# beaconboard2.net
KiCad netlist of a schematic drawn in EAGLE
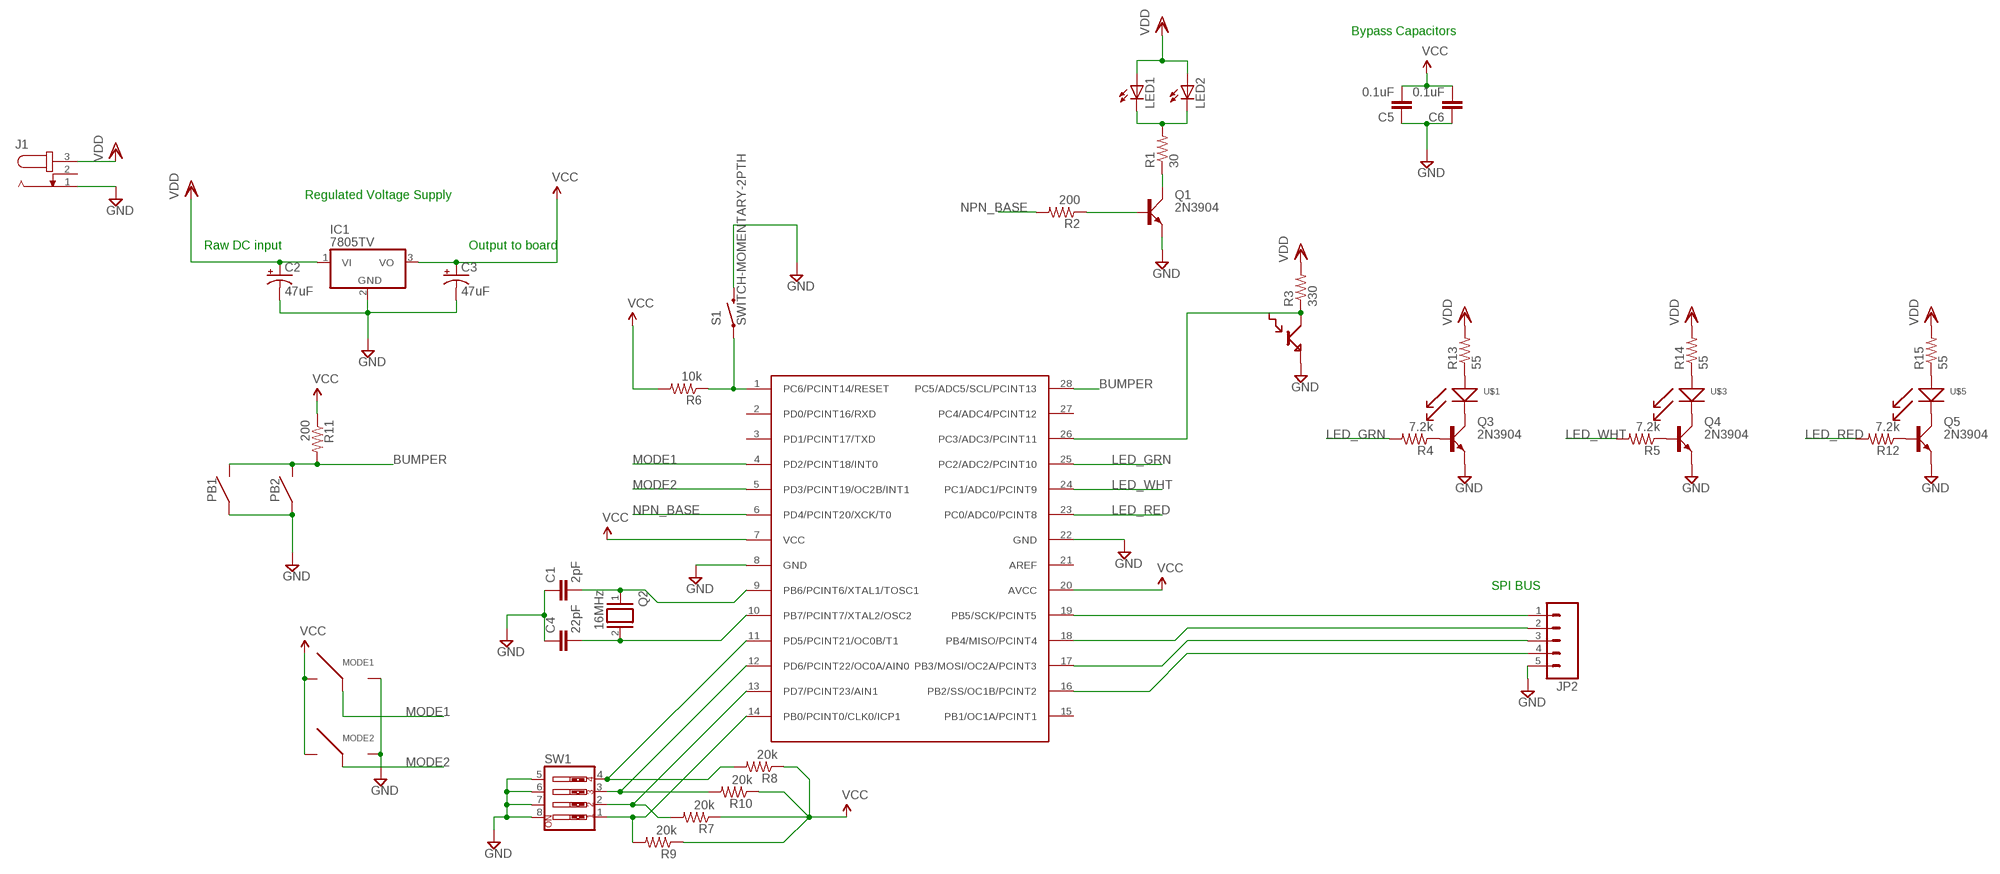
[diagram p0: schematic, sheet 1]

(export (version "E")
  (design (tool "Eeschema 10.0.6"))
  (components
    (comp (ref "C1")
      (value "2pF")
      (footprint "eagle-import:CAP-PTH-SMALL")
      (libsource (lib "eagle-import") (part "CAPPTH"))
    )
    (comp (ref "C2")
      (value "47uF")
      (footprint "eagle-import:CPOL-RADIAL-10UF-25V")
      (libsource (lib "eagle-import") (part "CAP_POLPTH2"))
    )
    (comp (ref "C3")
      (value "47uF")
      (footprint "eagle-import:CPOL-RADIAL-10UF-25V")
      (libsource (lib "eagle-import") (part "CAP_POLPTH2"))
    )
    (comp (ref "C4")
      (value "22pF")
      (footprint "eagle-import:CAP-PTH-SMALL")
      (libsource (lib "eagle-import") (part "CAPPTH"))
    )
    (comp (ref "C5")
      (value "0.1uF")
      (footprint "eagle-import:CAP-PTH-5MM")
      (libsource (lib "eagle-import") (part "CAPPTH1"))
    )
    (comp (ref "C6")
      (value "0.1uF")
      (footprint "eagle-import:CAP-PTH-5MM")
      (libsource (lib "eagle-import") (part "CAPPTH1"))
    )
    (comp (ref "IC1")
      (value "7805TV")
      (footprint "eagle-import:TO220V")
      (libsource (lib "eagle-import") (part "78TV05"))
    )
    (comp (ref "J1")
      (value "JACK-PLUG1")
      (footprint "eagle-import:SPC4078")
      (libsource (lib "eagle-import") (part "JACK-PLUG1"))
    )
    (comp (ref "JP2")
      (value "M05LOCK_LONGPADS")
      (footprint "eagle-import:1X05_LOCK_LONGPADS")
      (libsource (lib "eagle-import") (part "M05LOCK_LONGPADS"))
    )
    (comp (ref "LED1")
      (value "LED-2AC-CP41B-WES")
      (footprint "eagle-import:CP41B")
      (libsource (lib "eagle-import") (part "LED-2AC-CP41B-WES"))
    )
    (comp (ref "LED2")
      (value "LED-2AC-CP41B-WES")
      (footprint "eagle-import:CP41B")
      (libsource (lib "eagle-import") (part "LED-2AC-CP41B-WES"))
    )
    (comp (ref "MODE1")
      (value "SPD_SLIDE_SWITCH")
      (footprint "eagle-import:SPDT_SLIDE_SWITCH")
      (libsource (lib "eagle-import") (part "SPD_SLIDE_SWITCH"))
    )
    (comp (ref "MODE2")
      (value "SPD_SLIDE_SWITCH")
      (footprint "eagle-import:SPDT_SLIDE_SWITCH")
      (libsource (lib "eagle-import") (part "SPD_SLIDE_SWITCH"))
    )
    (comp (ref "PB1")
      (value "D6_PUSHBUTTON")
      (footprint "eagle-import:D6_PUSH_BUTTON")
      (libsource (lib "eagle-import") (part "D6_PUSHBUTTON"))
    )
    (comp (ref "PB2")
      (value "D6_PUSHBUTTON")
      (footprint "eagle-import:D6_PUSH_BUTTON")
      (libsource (lib "eagle-import") (part "D6_PUSHBUTTON"))
    )
    (comp (ref "Q1")
      (value "2N3904")
      (footprint "eagle-import:TO92D")
      (libsource (lib "eagle-import") (part "2N3904"))
    )
    (comp (ref "Q2")
      (value "16MHz")
      (footprint "eagle-import:QS")
      (libsource (lib "eagle-import") (part "XTAL/S"))
    )
    (comp (ref "Q3")
      (value "2N3904")
      (footprint "eagle-import:TO92D")
      (libsource (lib "eagle-import") (part "2N3904"))
    )
    (comp (ref "Q4")
      (value "2N3904")
      (footprint "eagle-import:TO92D")
      (libsource (lib "eagle-import") (part "2N3904"))
    )
    (comp (ref "Q5")
      (value "2N3904")
      (footprint "eagle-import:TO92D")
      (libsource (lib "eagle-import") (part "2N3904"))
    )
    (comp (ref "R1")
      (value "30")
      (footprint "eagle-import:AXIAL-0.4")
      (libsource (lib "eagle-import") (part "RESISTORPTH-1/4W"))
    )
    (comp (ref "R2")
      (value "200")
      (footprint "eagle-import:AXIAL-0.4")
      (libsource (lib "eagle-import") (part "RESISTORPTH-1/4W"))
    )
    (comp (ref "R3")
      (value "330")
      (footprint "eagle-import:AXIAL-0.4")
      (libsource (lib "eagle-import") (part "RESISTORPTH-1/4W"))
    )
    (comp (ref "R4")
      (value "7.2k")
      (footprint "eagle-import:AXIAL-0.4")
      (libsource (lib "eagle-import") (part "RESISTORPTH-1/4W"))
    )
    (comp (ref "R5")
      (value "7.2k")
      (footprint "eagle-import:AXIAL-0.4")
      (libsource (lib "eagle-import") (part "RESISTORPTH-1/4W"))
    )
    (comp (ref "R6")
      (value "10k")
      (footprint "eagle-import:AXIAL-0.4")
      (libsource (lib "eagle-import") (part "RESISTORPTH-1/4W"))
    )
    (comp (ref "R7")
      (value "20k")
      (footprint "eagle-import:AXIAL-0.4")
      (libsource (lib "eagle-import") (part "RESISTORPTH-1/4W"))
    )
    (comp (ref "R8")
      (value "20k")
      (footprint "eagle-import:AXIAL-0.4")
      (libsource (lib "eagle-import") (part "RESISTORPTH-1/4W"))
    )
    (comp (ref "R9")
      (value "20k")
      (footprint "eagle-import:AXIAL-0.4")
      (libsource (lib "eagle-import") (part "RESISTORPTH-1/4W"))
    )
    (comp (ref "R10")
      (value "20k")
      (footprint "eagle-import:AXIAL-0.4")
      (libsource (lib "eagle-import") (part "RESISTORPTH-1/4W"))
    )
    (comp (ref "R11")
      (value "200")
      (footprint "eagle-import:AXIAL-0.4")
      (libsource (lib "eagle-import") (part "RESISTORPTH-1/4W"))
    )
    (comp (ref "R12")
      (value "7.2k")
      (footprint "eagle-import:AXIAL-0.4")
      (libsource (lib "eagle-import") (part "RESISTORPTH-1/4W"))
    )
    (comp (ref "R13")
      (value "55")
      (footprint "eagle-import:AXIAL-0.4")
      (libsource (lib "eagle-import") (part "RESISTORPTH-1/4W"))
    )
    (comp (ref "R14")
      (value "55")
      (footprint "eagle-import:AXIAL-0.4")
      (libsource (lib "eagle-import") (part "RESISTORPTH-1/4W"))
    )
    (comp (ref "R15")
      (value "55")
      (footprint "eagle-import:AXIAL-0.4")
      (libsource (lib "eagle-import") (part "RESISTORPTH-1/4W"))
    )
    (comp (ref "S1")
      (value "SWITCH-MOMENTARY-2PTH")
      (footprint "eagle-import:TACTILE-PTH")
      (libsource (lib "eagle-import") (part "SWITCH-MOMENTARY-2PTH"))
    )
    (comp (ref "SW1")
      (value "SW_DIP-4")
      (footprint "eagle-import:EDG-04")
      (libsource (lib "eagle-import") (part "SW_DIP-4"))
    )
    (comp (ref "U$1")
      (value "8MM_LED")
      (footprint "eagle-import:8MM_LED")
      (libsource (lib "eagle-import") (part "8MM_LED"))
    )
    (comp (ref "U$2")
      (value "BPW77NA")
      (footprint "eagle-import:TO-18")
      (libsource (lib "eagle-import") (part "BPW77NA"))
    )
    (comp (ref "U$3")
      (value "8MM_LED")
      (footprint "eagle-import:8MM_LED")
      (libsource (lib "eagle-import") (part "8MM_LED"))
    )
    (comp (ref "U$4")
      (value "ATMEGA328")
      (footprint "eagle-import:DIL28-3")
      (libsource (lib "eagle-import") (part "ATMEGA328"))
    )
    (comp (ref "U$5")
      (value "8MM_LED")
      (footprint "eagle-import:8MM_LED")
      (libsource (lib "eagle-import") (part "8MM_LED"))
    )
  )
  (nets
    (net (code "1") (name "/BUMPER") (class "Default")
      (node (ref "PB1") (pin "3") (pinfunction "2_3") (pintype "bidirectional"))
      (node (ref "PB1") (pin "4") (pinfunction "2_4") (pintype "bidirectional"))
      (node (ref "PB2") (pin "3") (pinfunction "2_3") (pintype "bidirectional"))
      (node (ref "PB2") (pin "4") (pinfunction "2_4") (pintype "bidirectional"))
      (node (ref "R11") (pin "P$2") (pinfunction "2_P$2") (pintype "passive"))
      (node (ref "U$4") (pin "28") (pinfunction "PC5/ADC5/SCL/PCINT13_28") (pintype "bidirectional"))
    )
    (net (code "2") (name "/LED_GRN") (class "Default")
      (node (ref "R4") (pin "P$2") (pinfunction "2_P$2") (pintype "passive"))
      (node (ref "U$4") (pin "25") (pinfunction "PC2/ADC2/PCINT10_25") (pintype "bidirectional"))
    )
    (net (code "3") (name "/LED_RED") (class "Default")
      (node (ref "R12") (pin "P$2") (pinfunction "2_P$2") (pintype "passive"))
      (node (ref "U$4") (pin "23") (pinfunction "PC0/ADC0/PCINT8_23") (pintype "bidirectional"))
    )
    (net (code "4") (name "/LED_WHT") (class "Default")
      (node (ref "R5") (pin "P$2") (pinfunction "2_P$2") (pintype "passive"))
      (node (ref "U$4") (pin "24") (pinfunction "PC1/ADC1/PCINT9_24") (pintype "bidirectional"))
    )
    (net (code "5") (name "/MODE1") (class "Default")
      (node (ref "MODE1") (pin "2") (pinfunction "2_2") (pintype "bidirectional"))
      (node (ref "U$4") (pin "4") (pinfunction "PD2/PCINT18/INT0_4") (pintype "bidirectional"))
    )
    (net (code "6") (name "/MODE2") (class "Default")
      (node (ref "MODE2") (pin "2") (pinfunction "2_2") (pintype "bidirectional"))
      (node (ref "U$4") (pin "5") (pinfunction "PD3/PCINT19/OC2B/INT1_5") (pintype "bidirectional"))
    )
    (net (code "7") (name "/NPN_BASE") (class "Default")
      (node (ref "R2") (pin "P$2") (pinfunction "2_P$2") (pintype "passive"))
      (node (ref "U$4") (pin "6") (pinfunction "PD4/PCINT20/XCK/T0_6") (pintype "bidirectional"))
    )
    (net (code "8") (name "GND") (class "Default")
      (node (ref "C1") (pin "1") (pinfunction "1_1") (pintype "passive"))
      (node (ref "C2") (pin "2") (pinfunction "-_2") (pintype "passive"))
      (node (ref "C3") (pin "2") (pinfunction "-_2") (pintype "passive"))
      (node (ref "C4") (pin "1") (pinfunction "1_1") (pintype "passive"))
      (node (ref "C5") (pin "1") (pinfunction "1_1") (pintype "passive"))
      (node (ref "C6") (pin "1") (pinfunction "1_1") (pintype "passive"))
      (node (ref "IC1") (pin "2") (pinfunction "GND_2") (pintype "passive"))
      (node (ref "J1") (pin "1") (pinfunction "1_1") (pintype "passive"))
      (node (ref "JP2") (pin "5") (pinfunction "5_5") (pintype "passive"))
      (node (ref "MODE1") (pin "3") (pinfunction "3_3") (pintype "bidirectional"))
      (node (ref "MODE2") (pin "3") (pinfunction "3_3") (pintype "bidirectional"))
      (node (ref "PB1") (pin "1") (pinfunction "1_1") (pintype "bidirectional"))
      (node (ref "PB1") (pin "2") (pinfunction "1_2") (pintype "bidirectional"))
      (node (ref "PB2") (pin "1") (pinfunction "1_1") (pintype "bidirectional"))
      (node (ref "PB2") (pin "2") (pinfunction "1_2") (pintype "bidirectional"))
      (node (ref "Q1") (pin "E") (pinfunction "E_E") (pintype "passive"))
      (node (ref "Q3") (pin "E") (pinfunction "E_E") (pintype "passive"))
      (node (ref "Q4") (pin "E") (pinfunction "E_E") (pintype "passive"))
      (node (ref "Q5") (pin "E") (pinfunction "E_E") (pintype "passive"))
      (node (ref "S1") (pin "3") (pinfunction "2_3") (pintype "passive"))
      (node (ref "SW1") (pin "5") (pinfunction "5_5") (pintype "passive"))
      (node (ref "SW1") (pin "6") (pinfunction "6_6") (pintype "passive"))
      (node (ref "SW1") (pin "7") (pinfunction "7_7") (pintype "passive"))
      (node (ref "SW1") (pin "8") (pinfunction "8_8") (pintype "passive"))
      (node (ref "U$2") (pin "E") (pinfunction "E_E") (pintype "bidirectional"))
      (node (ref "U$4") (pin "22") (pinfunction "GND_22") (pintype "power_in"))
      (node (ref "U$4") (pin "8") (pinfunction "GND_8") (pintype "power_in"))
    )
    (net (code "9") (name "Net-(Q3-PadC)") (class "Default")
      (node (ref "Q3") (pin "C") (pinfunction "C_C") (pintype "passive"))
      (node (ref "U$1") (pin "NEG") (pinfunction "NEG_NEG") (pintype "bidirectional"))
    )
    (net (code "10") (name "Net-(Q4-PadC)") (class "Default")
      (node (ref "Q4") (pin "C") (pinfunction "C_C") (pintype "passive"))
      (node (ref "U$3") (pin "NEG") (pinfunction "NEG_NEG") (pintype "bidirectional"))
    )
    (net (code "11") (name "Net-(Q5-PadC)") (class "Default")
      (node (ref "Q5") (pin "C") (pinfunction "C_C") (pintype "passive"))
      (node (ref "U$5") (pin "NEG") (pinfunction "NEG_NEG") (pintype "bidirectional"))
    )
    (net (code "12") (name "Net-(R1-1)") (class "Default")
      (node (ref "Q1") (pin "C") (pinfunction "C_C") (pintype "passive"))
      (node (ref "R1") (pin "P$1") (pinfunction "1_P$1") (pintype "passive"))
    )
    (net (code "13") (name "Net-(R1-2)") (class "Default")
      (node (ref "LED1") (pin "1") (pinfunction "C_1") (pintype "passive"))
      (node (ref "LED1") (pin "4") (pinfunction "C_4") (pintype "passive"))
      (node (ref "LED2") (pin "1") (pinfunction "C_1") (pintype "passive"))
      (node (ref "LED2") (pin "4") (pinfunction "C_4") (pintype "passive"))
      (node (ref "R1") (pin "P$2") (pinfunction "2_P$2") (pintype "passive"))
    )
    (net (code "14") (name "Net-(R2-1)") (class "Default")
      (node (ref "Q1") (pin "B") (pinfunction "B_B") (pintype "passive"))
      (node (ref "R2") (pin "P$1") (pinfunction "1_P$1") (pintype "passive"))
    )
    (net (code "15") (name "Net-(R3-1)") (class "Default")
      (node (ref "R3") (pin "P$1") (pinfunction "1_P$1") (pintype "passive"))
      (node (ref "U$2") (pin "C") (pinfunction "C_C") (pintype "bidirectional"))
      (node (ref "U$4") (pin "26") (pinfunction "PC3/ADC3/PCINT11_26") (pintype "bidirectional"))
    )
    (net (code "16") (name "Net-(R4-1)") (class "Default")
      (node (ref "Q3") (pin "B") (pinfunction "B_B") (pintype "passive"))
      (node (ref "R4") (pin "P$1") (pinfunction "1_P$1") (pintype "passive"))
    )
    (net (code "17") (name "Net-(R5-1)") (class "Default")
      (node (ref "Q4") (pin "B") (pinfunction "B_B") (pintype "passive"))
      (node (ref "R5") (pin "P$1") (pinfunction "1_P$1") (pintype "passive"))
    )
    (net (code "18") (name "Net-(R6-1)") (class "Default")
      (node (ref "R6") (pin "P$1") (pinfunction "1_P$1") (pintype "passive"))
      (node (ref "S1") (pin "1") (pinfunction "1_1") (pintype "passive"))
      (node (ref "U$4") (pin "1") (pinfunction "PC6/PCINT14/RESET_1") (pintype "bidirectional"))
    )
    (net (code "19") (name "Net-(R7-2)") (class "Default")
      (node (ref "R7") (pin "P$2") (pinfunction "2_P$2") (pintype "passive"))
      (node (ref "SW1") (pin "2") (pinfunction "2_2") (pintype "passive"))
      (node (ref "U$4") (pin "13") (pinfunction "PD7/PCINT23/AIN1_13") (pintype "bidirectional"))
    )
    (net (code "20") (name "Net-(R8-2)") (class "Default")
      (node (ref "R8") (pin "P$2") (pinfunction "2_P$2") (pintype "passive"))
      (node (ref "SW1") (pin "4") (pinfunction "4_4") (pintype "passive"))
      (node (ref "U$4") (pin "11") (pinfunction "PD5/PCINT21/OC0B/T1_11") (pintype "bidirectional"))
    )
    (net (code "21") (name "Net-(R9-2)") (class "Default")
      (node (ref "R9") (pin "P$2") (pinfunction "2_P$2") (pintype "passive"))
      (node (ref "SW1") (pin "1") (pinfunction "1_1") (pintype "passive"))
      (node (ref "U$4") (pin "14") (pinfunction "PB0/PCINT0/CLK0/ICP1_14") (pintype "bidirectional"))
    )
    (net (code "22") (name "Net-(R10-2)") (class "Default")
      (node (ref "R10") (pin "P$2") (pinfunction "2_P$2") (pintype "passive"))
      (node (ref "SW1") (pin "3") (pinfunction "3_3") (pintype "passive"))
      (node (ref "U$4") (pin "12") (pinfunction "PD6/PCINT22/OC0A/AIN0_12") (pintype "bidirectional"))
    )
    (net (code "23") (name "Net-(R12-1)") (class "Default")
      (node (ref "Q5") (pin "B") (pinfunction "B_B") (pintype "passive"))
      (node (ref "R12") (pin "P$1") (pinfunction "1_P$1") (pintype "passive"))
    )
    (net (code "24") (name "Net-(R13-1)") (class "Default")
      (node (ref "R13") (pin "P$1") (pinfunction "1_P$1") (pintype "passive"))
      (node (ref "U$1") (pin "POS") (pinfunction "POS_POS") (pintype "bidirectional"))
    )
    (net (code "25") (name "Net-(R14-1)") (class "Default")
      (node (ref "R14") (pin "P$1") (pinfunction "1_P$1") (pintype "passive"))
      (node (ref "U$3") (pin "POS") (pinfunction "POS_POS") (pintype "bidirectional"))
    )
    (net (code "26") (name "Net-(R15-1)") (class "Default")
      (node (ref "R15") (pin "P$1") (pinfunction "1_P$1") (pintype "passive"))
      (node (ref "U$5") (pin "POS") (pinfunction "POS_POS") (pintype "bidirectional"))
    )
    (net (code "27") (name "Net-(U$4-PB2{slash}SS{slash}OC1B{slash}PCINT2)") (class "Default")
      (node (ref "JP2") (pin "4") (pinfunction "4_4") (pintype "passive"))
      (node (ref "U$4") (pin "16") (pinfunction "PB2/SS/OC1B/PCINT2_16") (pintype "bidirectional"))
    )
    (net (code "28") (name "Net-(U$4-PB3{slash}MOSI{slash}OC2A{slash}PCINT3)") (class "Default")
      (node (ref "JP2") (pin "3") (pinfunction "3_3") (pintype "passive"))
      (node (ref "U$4") (pin "17") (pinfunction "PB3/MOSI/OC2A/PCINT3_17") (pintype "bidirectional"))
    )
    (net (code "29") (name "Net-(U$4-PB4{slash}MISO{slash}PCINT4)") (class "Default")
      (node (ref "JP2") (pin "2") (pinfunction "2_2") (pintype "passive"))
      (node (ref "U$4") (pin "18") (pinfunction "PB4/MISO/PCINT4_18") (pintype "bidirectional"))
    )
    (net (code "30") (name "Net-(U$4-PB5{slash}SCK{slash}PCINT5)") (class "Default")
      (node (ref "JP2") (pin "1") (pinfunction "1_1") (pintype "passive"))
      (node (ref "U$4") (pin "19") (pinfunction "PB5/SCK/PCINT5_19") (pintype "bidirectional"))
    )
    (net (code "31") (name "Net-(U$4-PB6{slash}PCINT6{slash}XTAL1{slash}TOSC1)") (class "Default")
      (node (ref "C1") (pin "2") (pinfunction "2_2") (pintype "passive"))
      (node (ref "Q2") (pin "1") (pinfunction "1_1") (pintype "passive"))
      (node (ref "U$4") (pin "9") (pinfunction "PB6/PCINT6/XTAL1/TOSC1_9") (pintype "bidirectional"))
    )
    (net (code "32") (name "Net-(U$4-PB7{slash}PCINT7{slash}XTAL2{slash}OSC2)") (class "Default")
      (node (ref "C4") (pin "2") (pinfunction "2_2") (pintype "passive"))
      (node (ref "Q2") (pin "2") (pinfunction "2_2") (pintype "passive"))
      (node (ref "U$4") (pin "10") (pinfunction "PB7/PCINT7/XTAL2/OSC2_10") (pintype "bidirectional"))
    )
    (net (code "33") (name "VCC") (class "Default")
      (node (ref "C3") (pin "1") (pinfunction "+_1") (pintype "passive"))
      (node (ref "C5") (pin "2") (pinfunction "2_2") (pintype "passive"))
      (node (ref "C6") (pin "2") (pinfunction "2_2") (pintype "passive"))
      (node (ref "IC1") (pin "3") (pinfunction "VO_3") (pintype "passive"))
      (node (ref "MODE1") (pin "1") (pinfunction "1_1") (pintype "bidirectional"))
      (node (ref "MODE2") (pin "1") (pinfunction "1_1") (pintype "bidirectional"))
      (node (ref "R10") (pin "P$1") (pinfunction "1_P$1") (pintype "passive"))
      (node (ref "R11") (pin "P$1") (pinfunction "1_P$1") (pintype "passive"))
      (node (ref "R6") (pin "P$2") (pinfunction "2_P$2") (pintype "passive"))
      (node (ref "R7") (pin "P$1") (pinfunction "1_P$1") (pintype "passive"))
      (node (ref "R8") (pin "P$1") (pinfunction "1_P$1") (pintype "passive"))
      (node (ref "R9") (pin "P$1") (pinfunction "1_P$1") (pintype "passive"))
      (node (ref "U$4") (pin "20") (pinfunction "AVCC_20") (pintype "bidirectional"))
      (node (ref "U$4") (pin "7") (pinfunction "VCC_7") (pintype "power_in"))
    )
    (net (code "34") (name "VDD") (class "Default")
      (node (ref "C2") (pin "1") (pinfunction "+_1") (pintype "passive"))
      (node (ref "IC1") (pin "1") (pinfunction "VI_1") (pintype "input"))
      (node (ref "J1") (pin "3") (pinfunction "3_3") (pintype "passive"))
      (node (ref "LED1") (pin "2") (pinfunction "A_2") (pintype "passive"))
      (node (ref "LED1") (pin "3") (pinfunction "A_3") (pintype "passive"))
      (node (ref "LED2") (pin "2") (pinfunction "A_2") (pintype "passive"))
      (node (ref "LED2") (pin "3") (pinfunction "A_3") (pintype "passive"))
      (node (ref "R13") (pin "P$2") (pinfunction "2_P$2") (pintype "passive"))
      (node (ref "R14") (pin "P$2") (pinfunction "2_P$2") (pintype "passive"))
      (node (ref "R15") (pin "P$2") (pinfunction "2_P$2") (pintype "passive"))
      (node (ref "R3") (pin "P$2") (pinfunction "2_P$2") (pintype "passive"))
    )
    (net (code "35") (name "unconnected-(J1-Pad2)") (class "Default")
      (node (ref "J1") (pin "2") (pinfunction "2_2") (pintype "passive"))
    )
    (net (code "36") (name "unconnected-(U$4-AREF-Pad21)") (class "Default")
      (node (ref "U$4") (pin "21") (pinfunction "AREF_21") (pintype "bidirectional"))
    )
    (net (code "37") (name "unconnected-(U$4-PB1{slash}OC1A{slash}PCINT1-Pad15)") (class "Default")
      (node (ref "U$4") (pin "15") (pinfunction "PB1/OC1A/PCINT1_15") (pintype "bidirectional"))
    )
    (net (code "38") (name "unconnected-(U$4-PC4{slash}ADC4{slash}PCINT12-Pad27)") (class "Default")
      (node (ref "U$4") (pin "27") (pinfunction "PC4/ADC4/PCINT12_27") (pintype "bidirectional"))
    )
    (net (code "39") (name "unconnected-(U$4-PD0{slash}PCINT16{slash}RXD-Pad2)") (class "Default")
      (node (ref "U$4") (pin "2") (pinfunction "PD0/PCINT16/RXD_2") (pintype "bidirectional"))
    )
    (net (code "40") (name "unconnected-(U$4-PD1{slash}PCINT17{slash}TXD-Pad3)") (class "Default")
      (node (ref "U$4") (pin "3") (pinfunction "PD1/PCINT17/TXD_3") (pintype "bidirectional"))
    )
  )
)
